# fju_project.net
KiCad netlist of a schematic drawn in EAGLE
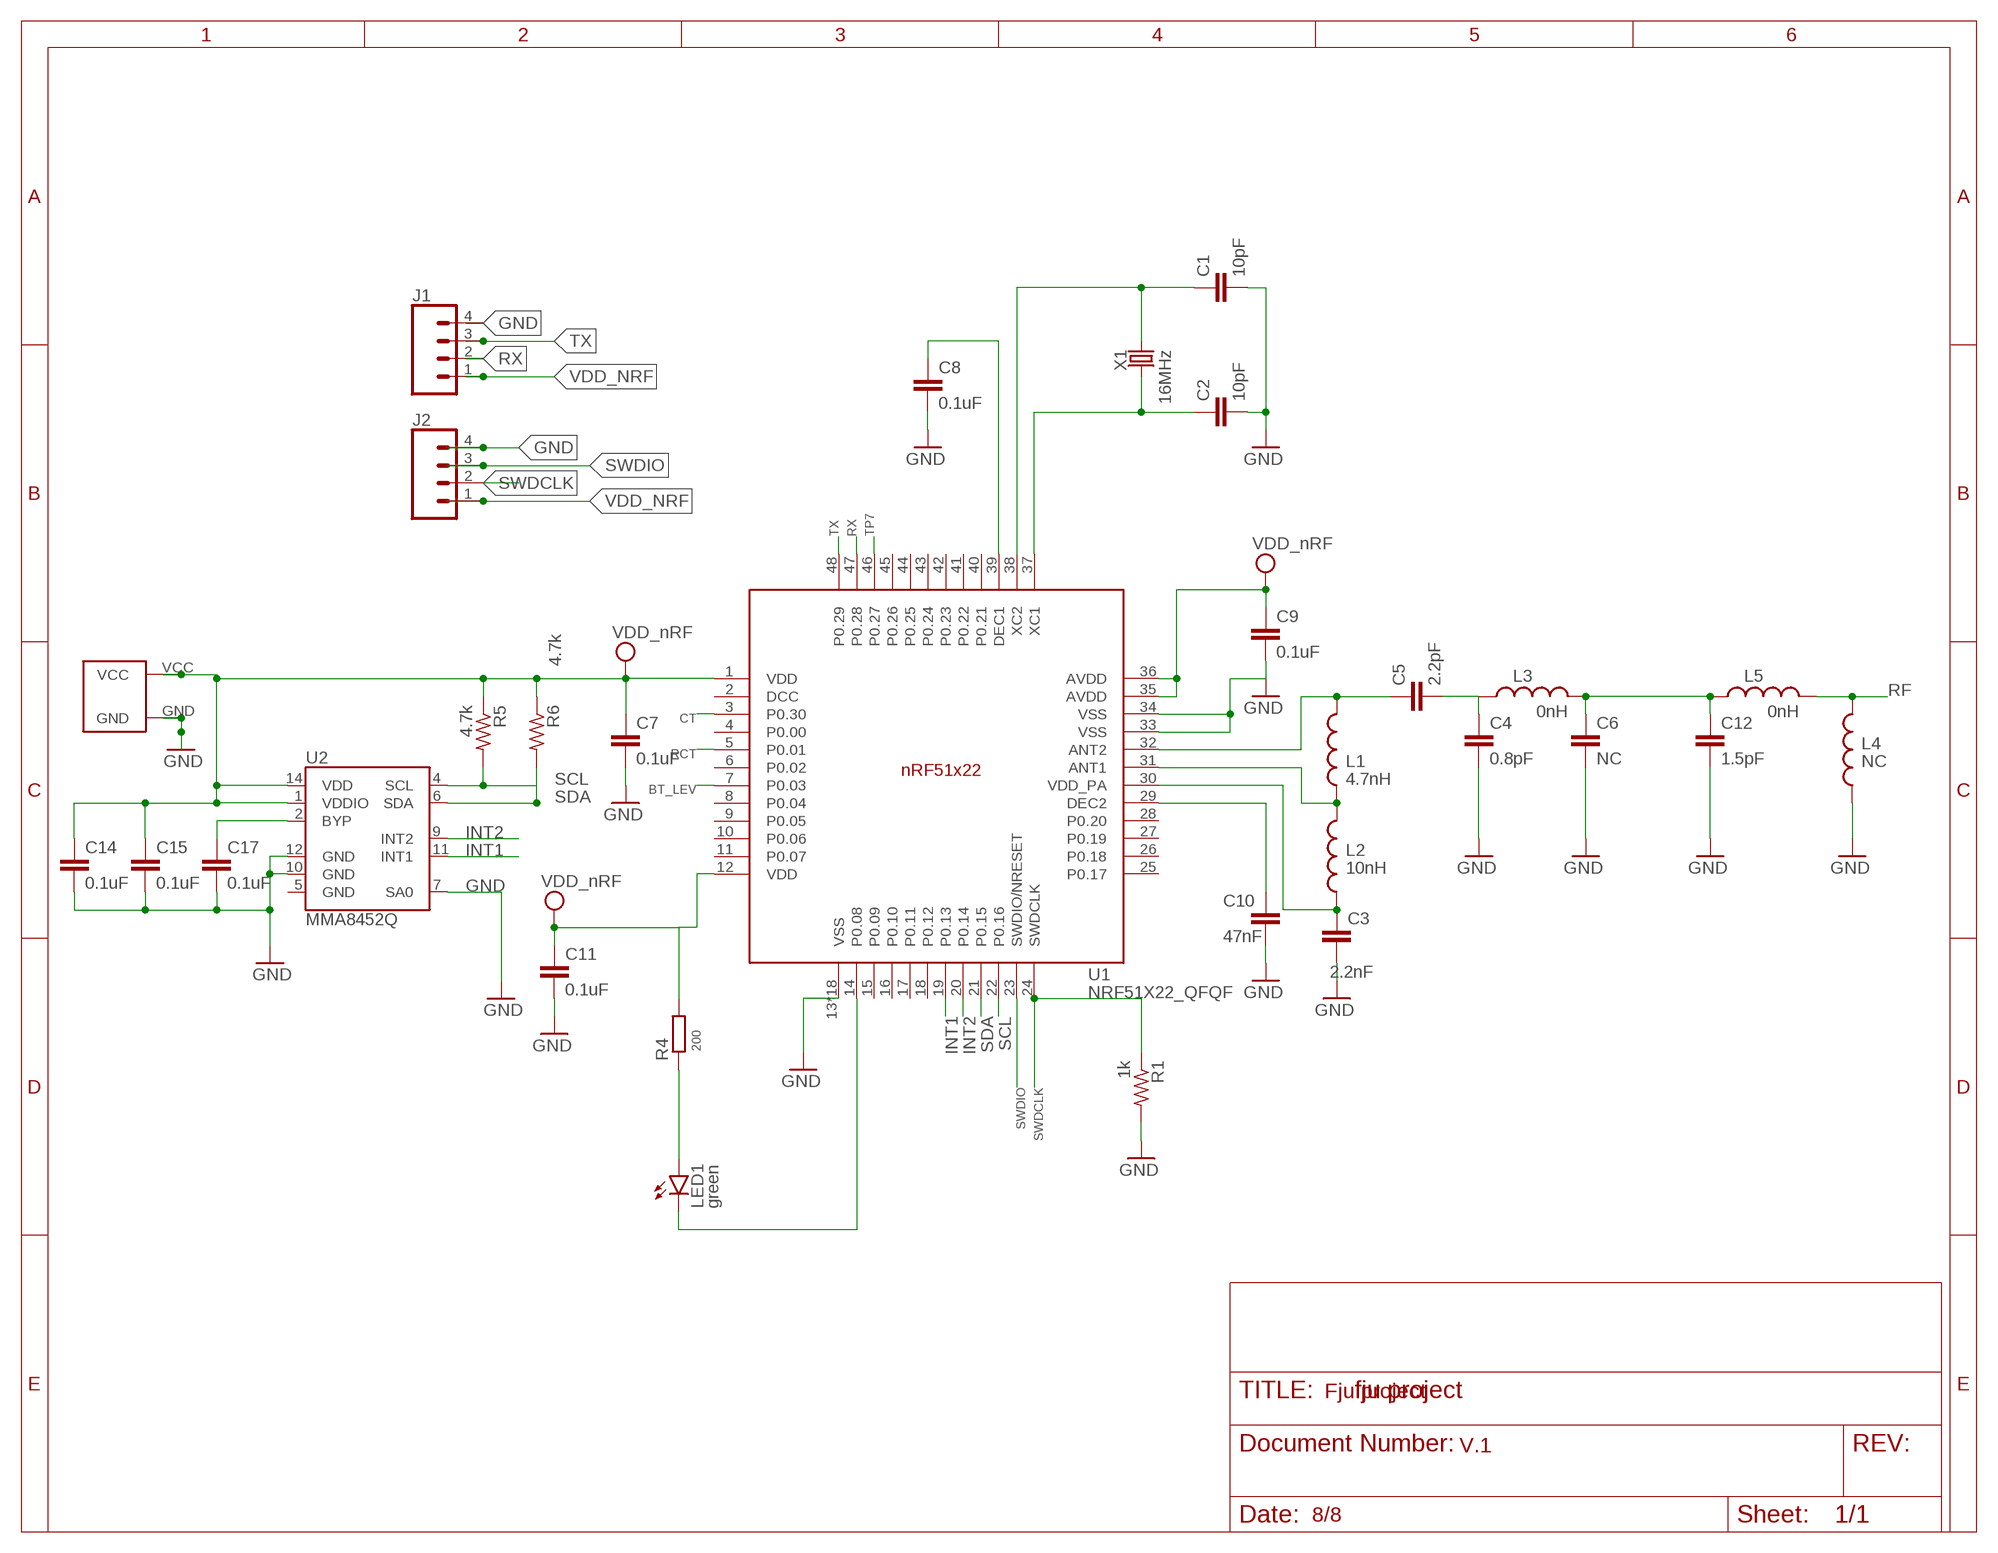
[diagram p0: schematic, sheet 1]

(export (version "E")
  (design (tool "Eeschema 10.0.6"))
  (components
    (comp (ref "C1")
      (value "10pF")
      (footprint "eagle-import:RESC0402_N")
      (libsource (lib "eagle-import") (part "CAPACITOR_0402_N"))
    )
    (comp (ref "C2")
      (value "10pF")
      (footprint "eagle-import:RESC0402_N")
      (libsource (lib "eagle-import") (part "CAPACITOR_0402_N"))
    )
    (comp (ref "C3")
      (value "2.2nF")
      (footprint "eagle-import:RESC0402_N")
      (libsource (lib "eagle-import") (part "CAPACITOR_0402_N"))
    )
    (comp (ref "C4")
      (value "0.8pF")
      (footprint "eagle-import:RESC0402_N")
      (libsource (lib "eagle-import") (part "CAPACITOR_0402_N"))
    )
    (comp (ref "C5")
      (value "2.2pF")
      (footprint "eagle-import:RESC0402_N")
      (libsource (lib "eagle-import") (part "CAPACITOR_0402_N"))
    )
    (comp (ref "C6")
      (value "NC")
      (footprint "eagle-import:RESC0402_N")
      (libsource (lib "eagle-import") (part "CAPACITOR_0402_N"))
    )
    (comp (ref "C7")
      (value "0.1uF")
      (footprint "eagle-import:RESC0402_N")
      (libsource (lib "eagle-import") (part "CAPACITOR_0402_N"))
    )
    (comp (ref "C8")
      (value "0.1uF")
      (footprint "eagle-import:RESC0402_N")
      (libsource (lib "eagle-import") (part "CAPACITOR_0402_N"))
    )
    (comp (ref "C9")
      (value "0.1uF")
      (footprint "eagle-import:RESC0402_N")
      (libsource (lib "eagle-import") (part "CAPACITOR_0402_N"))
    )
    (comp (ref "C10")
      (value "47nF")
      (footprint "eagle-import:RESC0402_N")
      (libsource (lib "eagle-import") (part "CAPACITOR_0402_N"))
    )
    (comp (ref "C11")
      (value "0.1uF")
      (footprint "eagle-import:RESC0402_N")
      (libsource (lib "eagle-import") (part "CAPACITOR_0402_N"))
    )
    (comp (ref "C12")
      (value "1.5pF")
      (footprint "eagle-import:RESC0402_N")
      (libsource (lib "eagle-import") (part "CAPACITOR_0402_N"))
    )
    (comp (ref "C14")
      (value "0.1uF")
      (footprint "eagle-import:RESC0402_N")
      (libsource (lib "eagle-import") (part "CAPACITOR_0402_N"))
    )
    (comp (ref "C15")
      (value "0.1uF")
      (footprint "eagle-import:RESC0402_N")
      (libsource (lib "eagle-import") (part "CAPACITOR_0402_N"))
    )
    (comp (ref "C17")
      (value "0.1uF")
      (footprint "eagle-import:RESC0402_N")
      (libsource (lib "eagle-import") (part "CAPACITOR_0402_N"))
    )
    (comp (ref "J1")
      (value "CONN_04")
      (footprint "eagle-import:1X04")
      (libsource (lib "eagle-import") (part "CONN_04"))
    )
    (comp (ref "J2")
      (value "CONN_04")
      (footprint "eagle-import:1X04")
      (libsource (lib "eagle-import") (part "CONN_04"))
    )
    (comp (ref "L1")
      (value "4.7nH")
      (footprint "eagle-import:RESC0402_N")
      (fields (field (name "MF") "BOURNS") (field (name "MPN") "CE201210-4N7J."))
      (libsource (lib "eagle-import") (part "INDUCTOR_0402_N"))
    )
    (comp (ref "L2")
      (value "10nH")
      (footprint "eagle-import:RESC0402_N")
      (libsource (lib "eagle-import") (part "INDUCTOR_0402_N"))
    )
    (comp (ref "L3")
      (value "0nH")
      (footprint "eagle-import:RESC0402_N")
      (libsource (lib "eagle-import") (part "INDUCTOR_0402_N"))
    )
    (comp (ref "L4")
      (value "NC")
      (footprint "eagle-import:RESC0402_N")
      (libsource (lib "eagle-import") (part "INDUCTOR_0402_N"))
    )
    (comp (ref "L5")
      (value "0nH")
      (footprint "eagle-import:RESC0402_N")
      (libsource (lib "eagle-import") (part "INDUCTOR_0402_N"))
    )
    (comp (ref "LED1")
      (value "green")
      (footprint "eagle-import:SML0603")
      (libsource (lib "eagle-import") (part "LEDSML0603"))
    )
    (comp (ref "R1")
      (value "1k")
      (footprint "eagle-import:R0402")
      (libsource (lib "eagle-import") (part "R-US_R0402"))
    )
    (comp (ref "R4")
      (value "200")
      (footprint "eagle-import:RESC0402_N")
      (libsource (lib "eagle-import") (part "RESISTOR_0402_N"))
    )
    (comp (ref "R5")
      (value "4.7k")
      (footprint "eagle-import:R0402")
      (libsource (lib "eagle-import") (part "R-US_R0402"))
    )
    (comp (ref "R6")
      (value "4.7k")
      (footprint "eagle-import:R0402")
      (libsource (lib "eagle-import") (part "R-US_R0402"))
    )
    (comp (ref "U$1")
      (value "CR2032")
      (footprint "eagle-import:CR2032-20MM")
      (libsource (lib "eagle-import") (part "CR2032"))
    )
    (comp (ref "U1")
      (value "NRF51X22_QFQF")
      (footprint "eagle-import:QFN40P600X600X90-48_N")
      (libsource (lib "eagle-import") (part "NRF51X22_QFQF"))
    )
    (comp (ref "U2")
      (value "MMA8452Q")
      (footprint "eagle-import:QFN-16_0.5MM")
      (libsource (lib "eagle-import") (part "MMA8452Q"))
    )
    (comp (ref "X1")
      (value "16MHz")
      (footprint "eagle-import:2.5X2.0_KX-6")
      (libsource (lib "eagle-import") (part "KX-6"))
    )
  )
  (nets
    (net (code "1") (name "/BT_LEV") (class "Default")
      (node (ref "U1") (pin "7") (pinfunction "P0.03_7") (pintype "bidirectional"))
    )
    (net (code "2") (name "/CT") (class "Default")
      (node (ref "U1") (pin "3") (pinfunction "P0.30_3") (pintype "bidirectional"))
    )
    (net (code "3") (name "/DCC") (class "Default")
      (node (ref "U1") (pin "2") (pinfunction "DCC_2") (pintype "power_in"))
    )
    (net (code "4") (name "/INT1") (class "Default")
      (node (ref "U1") (pin "19") (pinfunction "P0.13_19") (pintype "bidirectional"))
      (node (ref "U2") (pin "11") (pinfunction "INT1_11") (pintype "bidirectional"))
    )
    (net (code "5") (name "/INT2") (class "Default")
      (node (ref "U1") (pin "20") (pinfunction "P0.14_20") (pintype "bidirectional"))
      (node (ref "U2") (pin "9") (pinfunction "INT2_9") (pintype "bidirectional"))
    )
    (net (code "6") (name "/RCT") (class "Default")
      (node (ref "U1") (pin "5") (pinfunction "P0.01_5") (pintype "bidirectional"))
    )
    (net (code "7") (name "/RF") (class "Default")
      (node (ref "L4") (pin "2") (pinfunction "2_2") (pintype "passive"))
      (node (ref "L5") (pin "2") (pinfunction "2_2") (pintype "passive"))
    )
    (net (code "8") (name "/SCL") (class "Default")
      (node (ref "R5") (pin "2") (pinfunction "2_2") (pintype "passive"))
      (node (ref "U1") (pin "22") (pinfunction "P0.16_22") (pintype "bidirectional"))
      (node (ref "U2") (pin "4") (pinfunction "SCL_4") (pintype "bidirectional"))
    )
    (net (code "9") (name "/SDA") (class "Default")
      (node (ref "R6") (pin "2") (pinfunction "2_2") (pintype "passive"))
      (node (ref "U1") (pin "21") (pinfunction "P0.15_21") (pintype "bidirectional"))
      (node (ref "U2") (pin "6") (pinfunction "SDA_6") (pintype "bidirectional"))
    )
    (net (code "10") (name "/TP7") (class "Default")
      (node (ref "U1") (pin "46") (pinfunction "P0.27_46") (pintype "bidirectional"))
    )
    (net (code "11") (name "GND") (class "Default")
      (node (ref "C1") (pin "2") (pinfunction "2_2") (pintype "passive"))
      (node (ref "C10") (pin "2") (pinfunction "2_2") (pintype "passive"))
      (node (ref "C11") (pin "2") (pinfunction "2_2") (pintype "passive"))
      (node (ref "C12") (pin "2") (pinfunction "2_2") (pintype "passive"))
      (node (ref "C14") (pin "2") (pinfunction "2_2") (pintype "passive"))
      (node (ref "C15") (pin "2") (pinfunction "2_2") (pintype "passive"))
      (node (ref "C17") (pin "2") (pinfunction "2_2") (pintype "passive"))
      (node (ref "C2") (pin "2") (pinfunction "2_2") (pintype "passive"))
      (node (ref "C3") (pin "2") (pinfunction "2_2") (pintype "passive"))
      (node (ref "C4") (pin "2") (pinfunction "2_2") (pintype "passive"))
      (node (ref "C6") (pin "2") (pinfunction "2_2") (pintype "passive"))
      (node (ref "C7") (pin "2") (pinfunction "2_2") (pintype "passive"))
      (node (ref "C8") (pin "2") (pinfunction "2_2") (pintype "passive"))
      (node (ref "C9") (pin "2") (pinfunction "2_2") (pintype "passive"))
      (node (ref "J1") (pin "4") (pinfunction "4_4") (pintype "passive"))
      (node (ref "J2") (pin "4") (pinfunction "4_4") (pintype "passive"))
      (node (ref "L4") (pin "1") (pinfunction "1_1") (pintype "passive"))
      (node (ref "R1") (pin "2") (pinfunction "2_2") (pintype "passive"))
      (node (ref "U$1") (pin "GND") (pinfunction "GND_GND") (pintype "bidirectional"))
      (node (ref "U1") (pin "13") (pinfunction "VSS_13") (pintype "power_in"))
      (node (ref "U1") (pin "33") (pinfunction "VSS_33") (pintype "power_in"))
      (node (ref "U1") (pin "34") (pinfunction "VSS_34") (pintype "power_in"))
      (node (ref "U1") (pin "PAD") (pinfunction "VSS_PAD") (pintype "power_in"))
      (node (ref "U1") (pin "PAD@VIA01") (pinfunction "VSS_PAD@VIA01") (pintype "power_in"))
      (node (ref "U1") (pin "PAD@VIA02") (pinfunction "VSS_PAD@VIA02") (pintype "power_in"))
      (node (ref "U1") (pin "PAD@VIA03") (pinfunction "VSS_PAD@VIA03") (pintype "power_in"))
      (node (ref "U1") (pin "PAD@VIA04") (pinfunction "VSS_PAD@VIA04") (pintype "power_in"))
      (node (ref "U1") (pin "PAD@VIA05") (pinfunction "VSS_PAD@VIA05") (pintype "power_in"))
      (node (ref "U1") (pin "PAD@VIA06") (pinfunction "VSS_PAD@VIA06") (pintype "power_in"))
      (node (ref "U1") (pin "PAD@VIA07") (pinfunction "VSS_PAD@VIA07") (pintype "power_in"))
      (node (ref "U1") (pin "PAD@VIA08") (pinfunction "VSS_PAD@VIA08") (pintype "power_in"))
      (node (ref "U1") (pin "PAD@VIA09") (pinfunction "VSS_PAD@VIA09") (pintype "power_in"))
      (node (ref "U1") (pin "PAD@VIA10") (pinfunction "VSS_PAD@VIA10") (pintype "power_in"))
      (node (ref "U1") (pin "PAD@VIA11") (pinfunction "VSS_PAD@VIA11") (pintype "power_in"))
      (node (ref "U1") (pin "PAD@VIA12") (pinfunction "VSS_PAD@VIA12") (pintype "power_in"))
      (node (ref "U1") (pin "PAD@VIA13") (pinfunction "VSS_PAD@VIA13") (pintype "power_in"))
      (node (ref "U1") (pin "PAD@VIA14") (pinfunction "VSS_PAD@VIA14") (pintype "power_in"))
      (node (ref "U1") (pin "PAD@VIA15") (pinfunction "VSS_PAD@VIA15") (pintype "power_in"))
      (node (ref "U1") (pin "PAD@VIA16") (pinfunction "VSS_PAD@VIA16") (pintype "power_in"))
      (node (ref "U2") (pin "10") (pinfunction "GND_10") (pintype "bidirectional"))
      (node (ref "U2") (pin "12") (pinfunction "GND_12") (pintype "bidirectional"))
      (node (ref "U2") (pin "7") (pinfunction "SA0_7") (pintype "bidirectional"))
    )
    (net (code "12") (name "Net-(C4-Pad1)") (class "Default")
      (node (ref "C4") (pin "1") (pinfunction "1_1") (pintype "passive"))
      (node (ref "C5") (pin "2") (pinfunction "2_2") (pintype "passive"))
      (node (ref "L3") (pin "1") (pinfunction "1_1") (pintype "passive"))
    )
    (net (code "13") (name "Net-(C12-Pad1)") (class "Default")
      (node (ref "C12") (pin "1") (pinfunction "1_1") (pintype "passive"))
      (node (ref "C6") (pin "1") (pinfunction "1_1") (pintype "passive"))
      (node (ref "L3") (pin "2") (pinfunction "2_2") (pintype "passive"))
      (node (ref "L5") (pin "1") (pinfunction "1_1") (pintype "passive"))
    )
    (net (code "14") (name "Net-(LED1-PadA)") (class "Default")
      (node (ref "LED1") (pin "A") (pinfunction "A_A") (pintype "passive"))
      (node (ref "R4") (pin "1") (pinfunction "1_1") (pintype "passive"))
    )
    (net (code "15") (name "Net-(U1-ANT1)") (class "Default")
      (node (ref "L1") (pin "1") (pinfunction "1_1") (pintype "passive"))
      (node (ref "L2") (pin "2") (pinfunction "2_2") (pintype "passive"))
      (node (ref "U1") (pin "31") (pinfunction "ANT1_31") (pintype "bidirectional"))
    )
    (net (code "16") (name "Net-(U1-ANT2)") (class "Default")
      (node (ref "C5") (pin "1") (pinfunction "1_1") (pintype "passive"))
      (node (ref "L1") (pin "2") (pinfunction "2_2") (pintype "passive"))
      (node (ref "U1") (pin "32") (pinfunction "ANT2_32") (pintype "bidirectional"))
    )
    (net (code "17") (name "Net-(U1-DEC1)") (class "Default")
      (node (ref "C8") (pin "1") (pinfunction "1_1") (pintype "passive"))
      (node (ref "U1") (pin "39") (pinfunction "DEC1_39") (pintype "power_in"))
    )
    (net (code "18") (name "Net-(U1-DEC2)") (class "Default")
      (node (ref "C10") (pin "1") (pinfunction "1_1") (pintype "passive"))
      (node (ref "U1") (pin "29") (pinfunction "DEC2_29") (pintype "power_in"))
    )
    (net (code "19") (name "Net-(U1-P0.08)") (class "Default")
      (node (ref "LED1") (pin "C") (pinfunction "C_C") (pintype "passive"))
      (node (ref "U1") (pin "14") (pinfunction "P0.08_14") (pintype "bidirectional"))
    )
    (net (code "20") (name "Net-(U1-VDD_PA)") (class "Default")
      (node (ref "C3") (pin "1") (pinfunction "1_1") (pintype "passive"))
      (node (ref "L2") (pin "1") (pinfunction "1_1") (pintype "passive"))
      (node (ref "U1") (pin "30") (pinfunction "VDD_PA_30") (pintype "power_in"))
    )
    (net (code "21") (name "Net-(U1-XC1)") (class "Default")
      (node (ref "C2") (pin "1") (pinfunction "1_1") (pintype "passive"))
      (node (ref "U1") (pin "37") (pinfunction "XC1_37") (pintype "bidirectional"))
      (node (ref "X1") (pin "3") (pinfunction "2_3") (pintype "passive"))
    )
    (net (code "22") (name "Net-(U1-XC2)") (class "Default")
      (node (ref "C1") (pin "1") (pinfunction "1_1") (pintype "passive"))
      (node (ref "U1") (pin "38") (pinfunction "XC2_38") (pintype "bidirectional"))
      (node (ref "X1") (pin "1") (pinfunction "1_1") (pintype "passive"))
    )
    (net (code "23") (name "Net-(U2-BYP)") (class "Default")
      (node (ref "C17") (pin "1") (pinfunction "1_1") (pintype "passive"))
      (node (ref "U2") (pin "2") (pinfunction "BYP_2") (pintype "bidirectional"))
    )
    (net (code "24") (name "RX") (class "Default")
      (node (ref "J1") (pin "2") (pinfunction "2_2") (pintype "passive"))
      (node (ref "U1") (pin "47") (pinfunction "P0.28_47") (pintype "bidirectional"))
    )
    (net (code "25") (name "SWDCLK") (class "Default")
      (node (ref "J2") (pin "2") (pinfunction "2_2") (pintype "passive"))
      (node (ref "R1") (pin "1") (pinfunction "1_1") (pintype "passive"))
      (node (ref "U1") (pin "24") (pinfunction "SWDCLK_24") (pintype "input"))
    )
    (net (code "26") (name "SWDIO") (class "Default")
      (node (ref "J2") (pin "3") (pinfunction "3_3") (pintype "passive"))
      (node (ref "U1") (pin "23") (pinfunction "SWDIO/NRESET_23") (pintype "bidirectional"))
    )
    (net (code "27") (name "TX") (class "Default")
      (node (ref "J1") (pin "3") (pinfunction "3_3") (pintype "passive"))
      (node (ref "U1") (pin "48") (pinfunction "P0.29_48") (pintype "bidirectional"))
    )
    (net (code "28") (name "VDD_NRF") (class "Default")
      (node (ref "C11") (pin "1") (pinfunction "1_1") (pintype "passive"))
      (node (ref "C14") (pin "1") (pinfunction "1_1") (pintype "passive"))
      (node (ref "C15") (pin "1") (pinfunction "1_1") (pintype "passive"))
      (node (ref "C7") (pin "1") (pinfunction "1_1") (pintype "passive"))
      (node (ref "C9") (pin "1") (pinfunction "1_1") (pintype "passive"))
      (node (ref "J1") (pin "1") (pinfunction "1_1") (pintype "passive"))
      (node (ref "J2") (pin "1") (pinfunction "1_1") (pintype "passive"))
      (node (ref "R4") (pin "2") (pinfunction "2_2") (pintype "passive"))
      (node (ref "R5") (pin "1") (pinfunction "1_1") (pintype "passive"))
      (node (ref "R6") (pin "1") (pinfunction "1_1") (pintype "passive"))
      (node (ref "U$1") (pin "VCC") (pinfunction "VCC_VCC") (pintype "bidirectional"))
      (node (ref "U1") (pin "1") (pinfunction "VDD_1") (pintype "power_in"))
      (node (ref "U1") (pin "12") (pinfunction "VDD_12") (pintype "power_in"))
      (node (ref "U1") (pin "35") (pinfunction "AVDD_35") (pintype "power_in"))
      (node (ref "U1") (pin "36") (pinfunction "AVDD_36") (pintype "power_in"))
      (node (ref "U2") (pin "1") (pinfunction "VDDIO_1") (pintype "bidirectional"))
      (node (ref "U2") (pin "14") (pinfunction "VDD_14") (pintype "bidirectional"))
    )
    (net (code "29") (name "unconnected-(U1-P0.00-Pad4)") (class "Default")
      (node (ref "U1") (pin "4") (pinfunction "P0.00_4") (pintype "bidirectional"))
    )
    (net (code "30") (name "unconnected-(U1-P0.02-Pad6)") (class "Default")
      (node (ref "U1") (pin "6") (pinfunction "P0.02_6") (pintype "bidirectional"))
    )
    (net (code "31") (name "unconnected-(U1-P0.04-Pad8)") (class "Default")
      (node (ref "U1") (pin "8") (pinfunction "P0.04_8") (pintype "bidirectional"))
    )
    (net (code "32") (name "unconnected-(U1-P0.05-Pad9)") (class "Default")
      (node (ref "U1") (pin "9") (pinfunction "P0.05_9") (pintype "bidirectional"))
    )
    (net (code "33") (name "unconnected-(U1-P0.06-Pad10)") (class "Default")
      (node (ref "U1") (pin "10") (pinfunction "P0.06_10") (pintype "bidirectional"))
    )
    (net (code "34") (name "unconnected-(U1-P0.07-Pad11)") (class "Default")
      (node (ref "U1") (pin "11") (pinfunction "P0.07_11") (pintype "bidirectional"))
    )
    (net (code "35") (name "unconnected-(U1-P0.09-Pad15)") (class "Default")
      (node (ref "U1") (pin "15") (pinfunction "P0.09_15") (pintype "bidirectional"))
    )
    (net (code "36") (name "unconnected-(U1-P0.10-Pad16)") (class "Default")
      (node (ref "U1") (pin "16") (pinfunction "P0.10_16") (pintype "bidirectional"))
    )
    (net (code "37") (name "unconnected-(U1-P0.11-Pad17)") (class "Default")
      (node (ref "U1") (pin "17") (pinfunction "P0.11_17") (pintype "bidirectional"))
    )
    (net (code "38") (name "unconnected-(U1-P0.12-Pad18)") (class "Default")
      (node (ref "U1") (pin "18") (pinfunction "P0.12_18") (pintype "bidirectional"))
    )
    (net (code "39") (name "unconnected-(U1-P0.17-Pad25)") (class "Default")
      (node (ref "U1") (pin "25") (pinfunction "P0.17_25") (pintype "bidirectional"))
    )
    (net (code "40") (name "unconnected-(U1-P0.18-Pad26)") (class "Default")
      (node (ref "U1") (pin "26") (pinfunction "P0.18_26") (pintype "bidirectional"))
    )
    (net (code "41") (name "unconnected-(U1-P0.19-Pad27)") (class "Default")
      (node (ref "U1") (pin "27") (pinfunction "P0.19_27") (pintype "bidirectional"))
    )
    (net (code "42") (name "unconnected-(U1-P0.20-Pad28)") (class "Default")
      (node (ref "U1") (pin "28") (pinfunction "P0.20_28") (pintype "bidirectional"))
    )
    (net (code "43") (name "unconnected-(U1-P0.21-Pad40)") (class "Default")
      (node (ref "U1") (pin "40") (pinfunction "P0.21_40") (pintype "bidirectional"))
    )
    (net (code "44") (name "unconnected-(U1-P0.22-Pad41)") (class "Default")
      (node (ref "U1") (pin "41") (pinfunction "P0.22_41") (pintype "bidirectional"))
    )
    (net (code "45") (name "unconnected-(U1-P0.23-Pad42)") (class "Default")
      (node (ref "U1") (pin "42") (pinfunction "P0.23_42") (pintype "bidirectional"))
    )
    (net (code "46") (name "unconnected-(U1-P0.24-Pad43)") (class "Default")
      (node (ref "U1") (pin "43") (pinfunction "P0.24_43") (pintype "bidirectional"))
    )
    (net (code "47") (name "unconnected-(U1-P0.25-Pad44)") (class "Default")
      (node (ref "U1") (pin "44") (pinfunction "P0.25_44") (pintype "bidirectional"))
    )
    (net (code "48") (name "unconnected-(U1-P0.26-Pad45)") (class "Default")
      (node (ref "U1") (pin "45") (pinfunction "P0.26_45") (pintype "bidirectional"))
    )
    (net (code "49") (name "unconnected-(U2-GND-Pad5)") (class "Default")
      (node (ref "U2") (pin "5") (pinfunction "GND_5") (pintype "bidirectional"))
    )
  )
)
